# SparkFun_Motor_Driver-TB6612FNG_v11.net
KiCad netlist of a schematic drawn in EAGLE
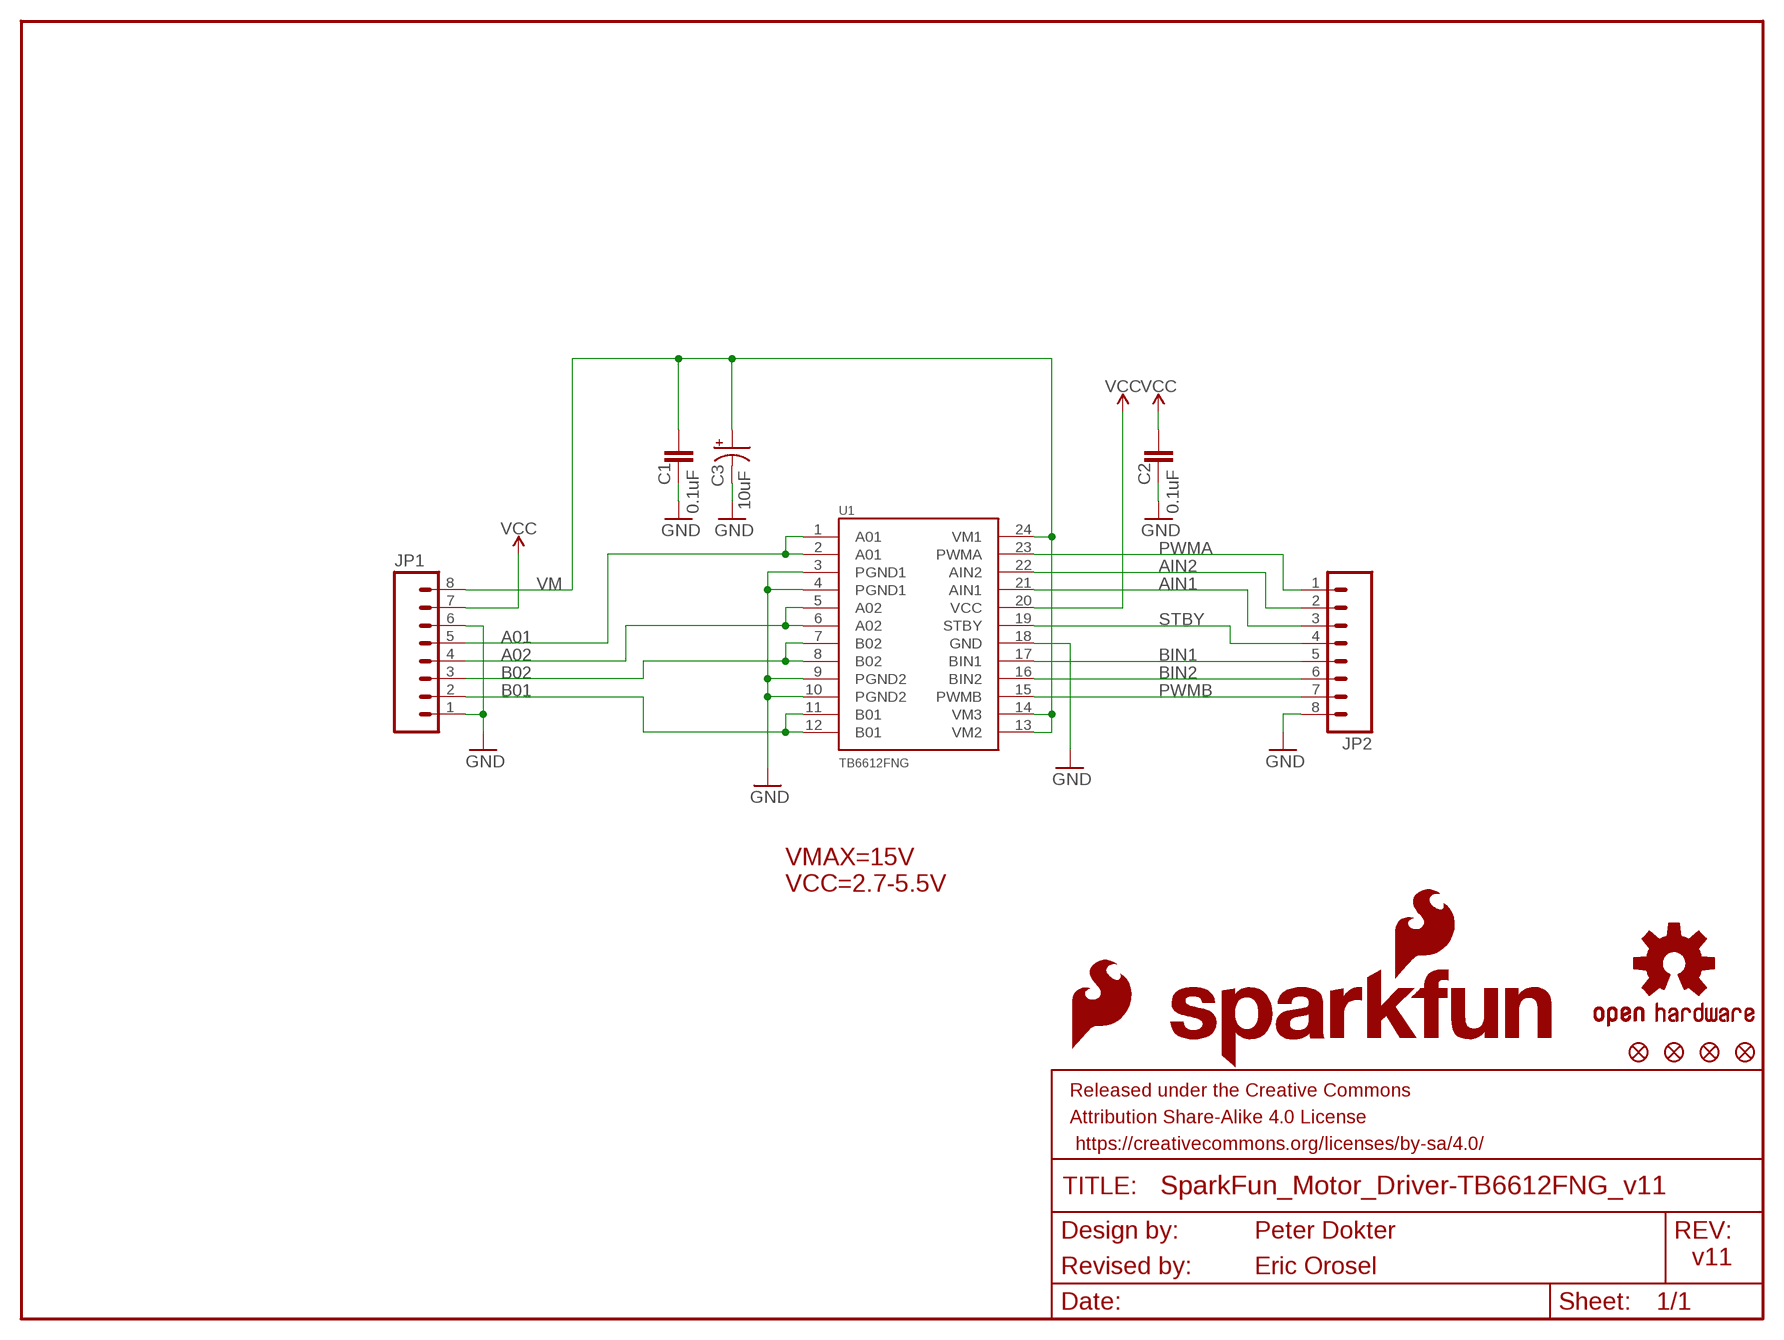
[diagram p0: schematic, sheet 1]

(export (version "E")
  (design (tool "Eeschema 10.0.6"))
  (components
    (comp (ref "C1")
      (value "0.1uF")
      (footprint "eagle-import:0402")
      (libsource (lib "eagle-import") (part "0.1UF-0402-16V-10%"))
    )
    (comp (ref "C2")
      (value "0.1uF")
      (footprint "eagle-import:0402")
      (libsource (lib "eagle-import") (part "0.1UF-0402-16V-10%"))
    )
    (comp (ref "C3")
      (value "10uF")
      (footprint "eagle-import:EIA3528")
      (libsource (lib "eagle-import") (part "10UF-POLAR-EIA3528-20V-10%(TANT)"))
    )
    (comp (ref "FD1")
      (value "FIDUCIALUFIDUCIAL")
      (footprint "eagle-import:FIDUCIAL-MICRO")
      (libsource (lib "eagle-import") (part "FIDUCIALUFIDUCIAL"))
    )
    (comp (ref "FD2")
      (value "FIDUCIALUFIDUCIAL")
      (footprint "eagle-import:FIDUCIAL-MICRO")
      (libsource (lib "eagle-import") (part "FIDUCIALUFIDUCIAL"))
    )
    (comp (ref "FD3")
      (value "FIDUCIALUFIDUCIAL")
      (footprint "eagle-import:FIDUCIAL-MICRO")
      (libsource (lib "eagle-import") (part "FIDUCIALUFIDUCIAL"))
    )
    (comp (ref "FD4")
      (value "FIDUCIALUFIDUCIAL")
      (footprint "eagle-import:FIDUCIAL-MICRO")
      (libsource (lib "eagle-import") (part "FIDUCIALUFIDUCIAL"))
    )
    (comp (ref "FRAME1")
      (value "FRAME-LETTER")
      (footprint "eagle-import:CREATIVE_COMMONS")
      (libsource (lib "eagle-import") (part "FRAME-LETTER"))
    )
    (comp (ref "JP1")
      (value "M0875_PERCENT_REDUCED")
      (footprint "eagle-import:1X08_OFFSET_REDUCED")
      (libsource (lib "eagle-import") (part "M0875_PERCENT_REDUCED"))
    )
    (comp (ref "JP2")
      (value "M0875_PERCENT_REDUCED")
      (footprint "eagle-import:1X08_OFFSET_REDUCED")
      (libsource (lib "eagle-import") (part "M0875_PERCENT_REDUCED"))
    )
    (comp (ref "LOGO1")
      (value "SFE_LOGO_FLAME.1_INCH")
      (footprint "eagle-import:SFE_LOGO_FLAME_.1")
      (libsource (lib "eagle-import") (part "SFE_LOGO_FLAME.1_INCH"))
    )
    (comp (ref "LOGO2")
      (value "OSHW-LOGOS")
      (footprint "eagle-import:OSHW-LOGO-S")
      (libsource (lib "eagle-import") (part "OSHW-LOGOS"))
    )
    (comp (ref "LOGO4")
      (value "SFE_LOGO_NAME_FLAME.1_INCH")
      (footprint "eagle-import:SFE_LOGO_NAME_FLAME_.1")
      (libsource (lib "eagle-import") (part "SFE_LOGO_NAME_FLAME.1_INCH"))
    )
    (comp (ref "U1")
      (value "TB6612FNG")
      (footprint "eagle-import:SSOP24")
      (libsource (lib "eagle-import") (part "TB6612FNG"))
    )
  )
  (nets
    (net (code "1") (name "/A01") (class "Default")
      (node (ref "JP1") (pin "5") (pinfunction "5_5") (pintype "passive"))
      (node (ref "U1") (pin "1") (pinfunction "A01_1") (pintype "bidirectional"))
      (node (ref "U1") (pin "2") (pinfunction "A01_2") (pintype "bidirectional"))
    )
    (net (code "2") (name "/A02") (class "Default")
      (node (ref "JP1") (pin "4") (pinfunction "4_4") (pintype "passive"))
      (node (ref "U1") (pin "5") (pinfunction "A02_5") (pintype "bidirectional"))
      (node (ref "U1") (pin "6") (pinfunction "A02_6") (pintype "bidirectional"))
    )
    (net (code "3") (name "/AIN1") (class "Default")
      (node (ref "JP2") (pin "3") (pinfunction "3_3") (pintype "passive"))
      (node (ref "U1") (pin "21") (pinfunction "AIN1_21") (pintype "bidirectional"))
    )
    (net (code "4") (name "/AIN2") (class "Default")
      (node (ref "JP2") (pin "2") (pinfunction "2_2") (pintype "passive"))
      (node (ref "U1") (pin "22") (pinfunction "AIN2_22") (pintype "bidirectional"))
    )
    (net (code "5") (name "/B01") (class "Default")
      (node (ref "JP1") (pin "2") (pinfunction "2_2") (pintype "passive"))
      (node (ref "U1") (pin "11") (pinfunction "B01_11") (pintype "bidirectional"))
      (node (ref "U1") (pin "12") (pinfunction "B01_12") (pintype "bidirectional"))
    )
    (net (code "6") (name "/B02") (class "Default")
      (node (ref "JP1") (pin "3") (pinfunction "3_3") (pintype "passive"))
      (node (ref "U1") (pin "7") (pinfunction "B02_7") (pintype "bidirectional"))
      (node (ref "U1") (pin "8") (pinfunction "B02_8") (pintype "bidirectional"))
    )
    (net (code "7") (name "/BIN1") (class "Default")
      (node (ref "JP2") (pin "5") (pinfunction "5_5") (pintype "passive"))
      (node (ref "U1") (pin "17") (pinfunction "BIN1_17") (pintype "bidirectional"))
    )
    (net (code "8") (name "/BIN2") (class "Default")
      (node (ref "JP2") (pin "6") (pinfunction "6_6") (pintype "passive"))
      (node (ref "U1") (pin "16") (pinfunction "BIN2_16") (pintype "bidirectional"))
    )
    (net (code "9") (name "/PWMA") (class "Default")
      (node (ref "JP2") (pin "1") (pinfunction "1_1") (pintype "passive"))
      (node (ref "U1") (pin "23") (pinfunction "PWMA_23") (pintype "bidirectional"))
    )
    (net (code "10") (name "/PWMB") (class "Default")
      (node (ref "JP2") (pin "7") (pinfunction "7_7") (pintype "passive"))
      (node (ref "U1") (pin "15") (pinfunction "PWMB_15") (pintype "bidirectional"))
    )
    (net (code "11") (name "/STBY") (class "Default")
      (node (ref "JP2") (pin "4") (pinfunction "4_4") (pintype "passive"))
      (node (ref "U1") (pin "19") (pinfunction "STBY_19") (pintype "bidirectional"))
    )
    (net (code "12") (name "/VM") (class "Default")
      (node (ref "C1") (pin "1") (pinfunction "1_1") (pintype "passive"))
      (node (ref "C3") (pin "A") (pinfunction "+_A") (pintype "passive"))
      (node (ref "JP1") (pin "8") (pinfunction "8_8") (pintype "passive"))
      (node (ref "U1") (pin "13") (pinfunction "VM2_13") (pintype "bidirectional"))
      (node (ref "U1") (pin "14") (pinfunction "VM3_14") (pintype "bidirectional"))
      (node (ref "U1") (pin "24") (pinfunction "VM1_24") (pintype "bidirectional"))
    )
    (net (code "13") (name "GND") (class "Default")
      (node (ref "C1") (pin "2") (pinfunction "2_2") (pintype "passive"))
      (node (ref "C2") (pin "2") (pinfunction "2_2") (pintype "passive"))
      (node (ref "C3") (pin "C") (pinfunction "-_C") (pintype "passive"))
      (node (ref "JP1") (pin "1") (pinfunction "1_1") (pintype "passive"))
      (node (ref "JP1") (pin "6") (pinfunction "6_6") (pintype "passive"))
      (node (ref "JP2") (pin "8") (pinfunction "8_8") (pintype "passive"))
      (node (ref "U1") (pin "10") (pinfunction "PGND2_10") (pintype "bidirectional"))
      (node (ref "U1") (pin "18") (pinfunction "GND_18") (pintype "bidirectional"))
      (node (ref "U1") (pin "3") (pinfunction "PGND1_3") (pintype "bidirectional"))
      (node (ref "U1") (pin "4") (pinfunction "PGND1_4") (pintype "bidirectional"))
      (node (ref "U1") (pin "9") (pinfunction "PGND2_9") (pintype "bidirectional"))
    )
    (net (code "14") (name "VCC") (class "Default")
      (node (ref "C2") (pin "1") (pinfunction "1_1") (pintype "passive"))
      (node (ref "JP1") (pin "7") (pinfunction "7_7") (pintype "passive"))
      (node (ref "U1") (pin "20") (pinfunction "VCC_20") (pintype "bidirectional"))
    )
  )
)
